# Main.net
KiCad netlist of a schematic drawn in Altium Designer
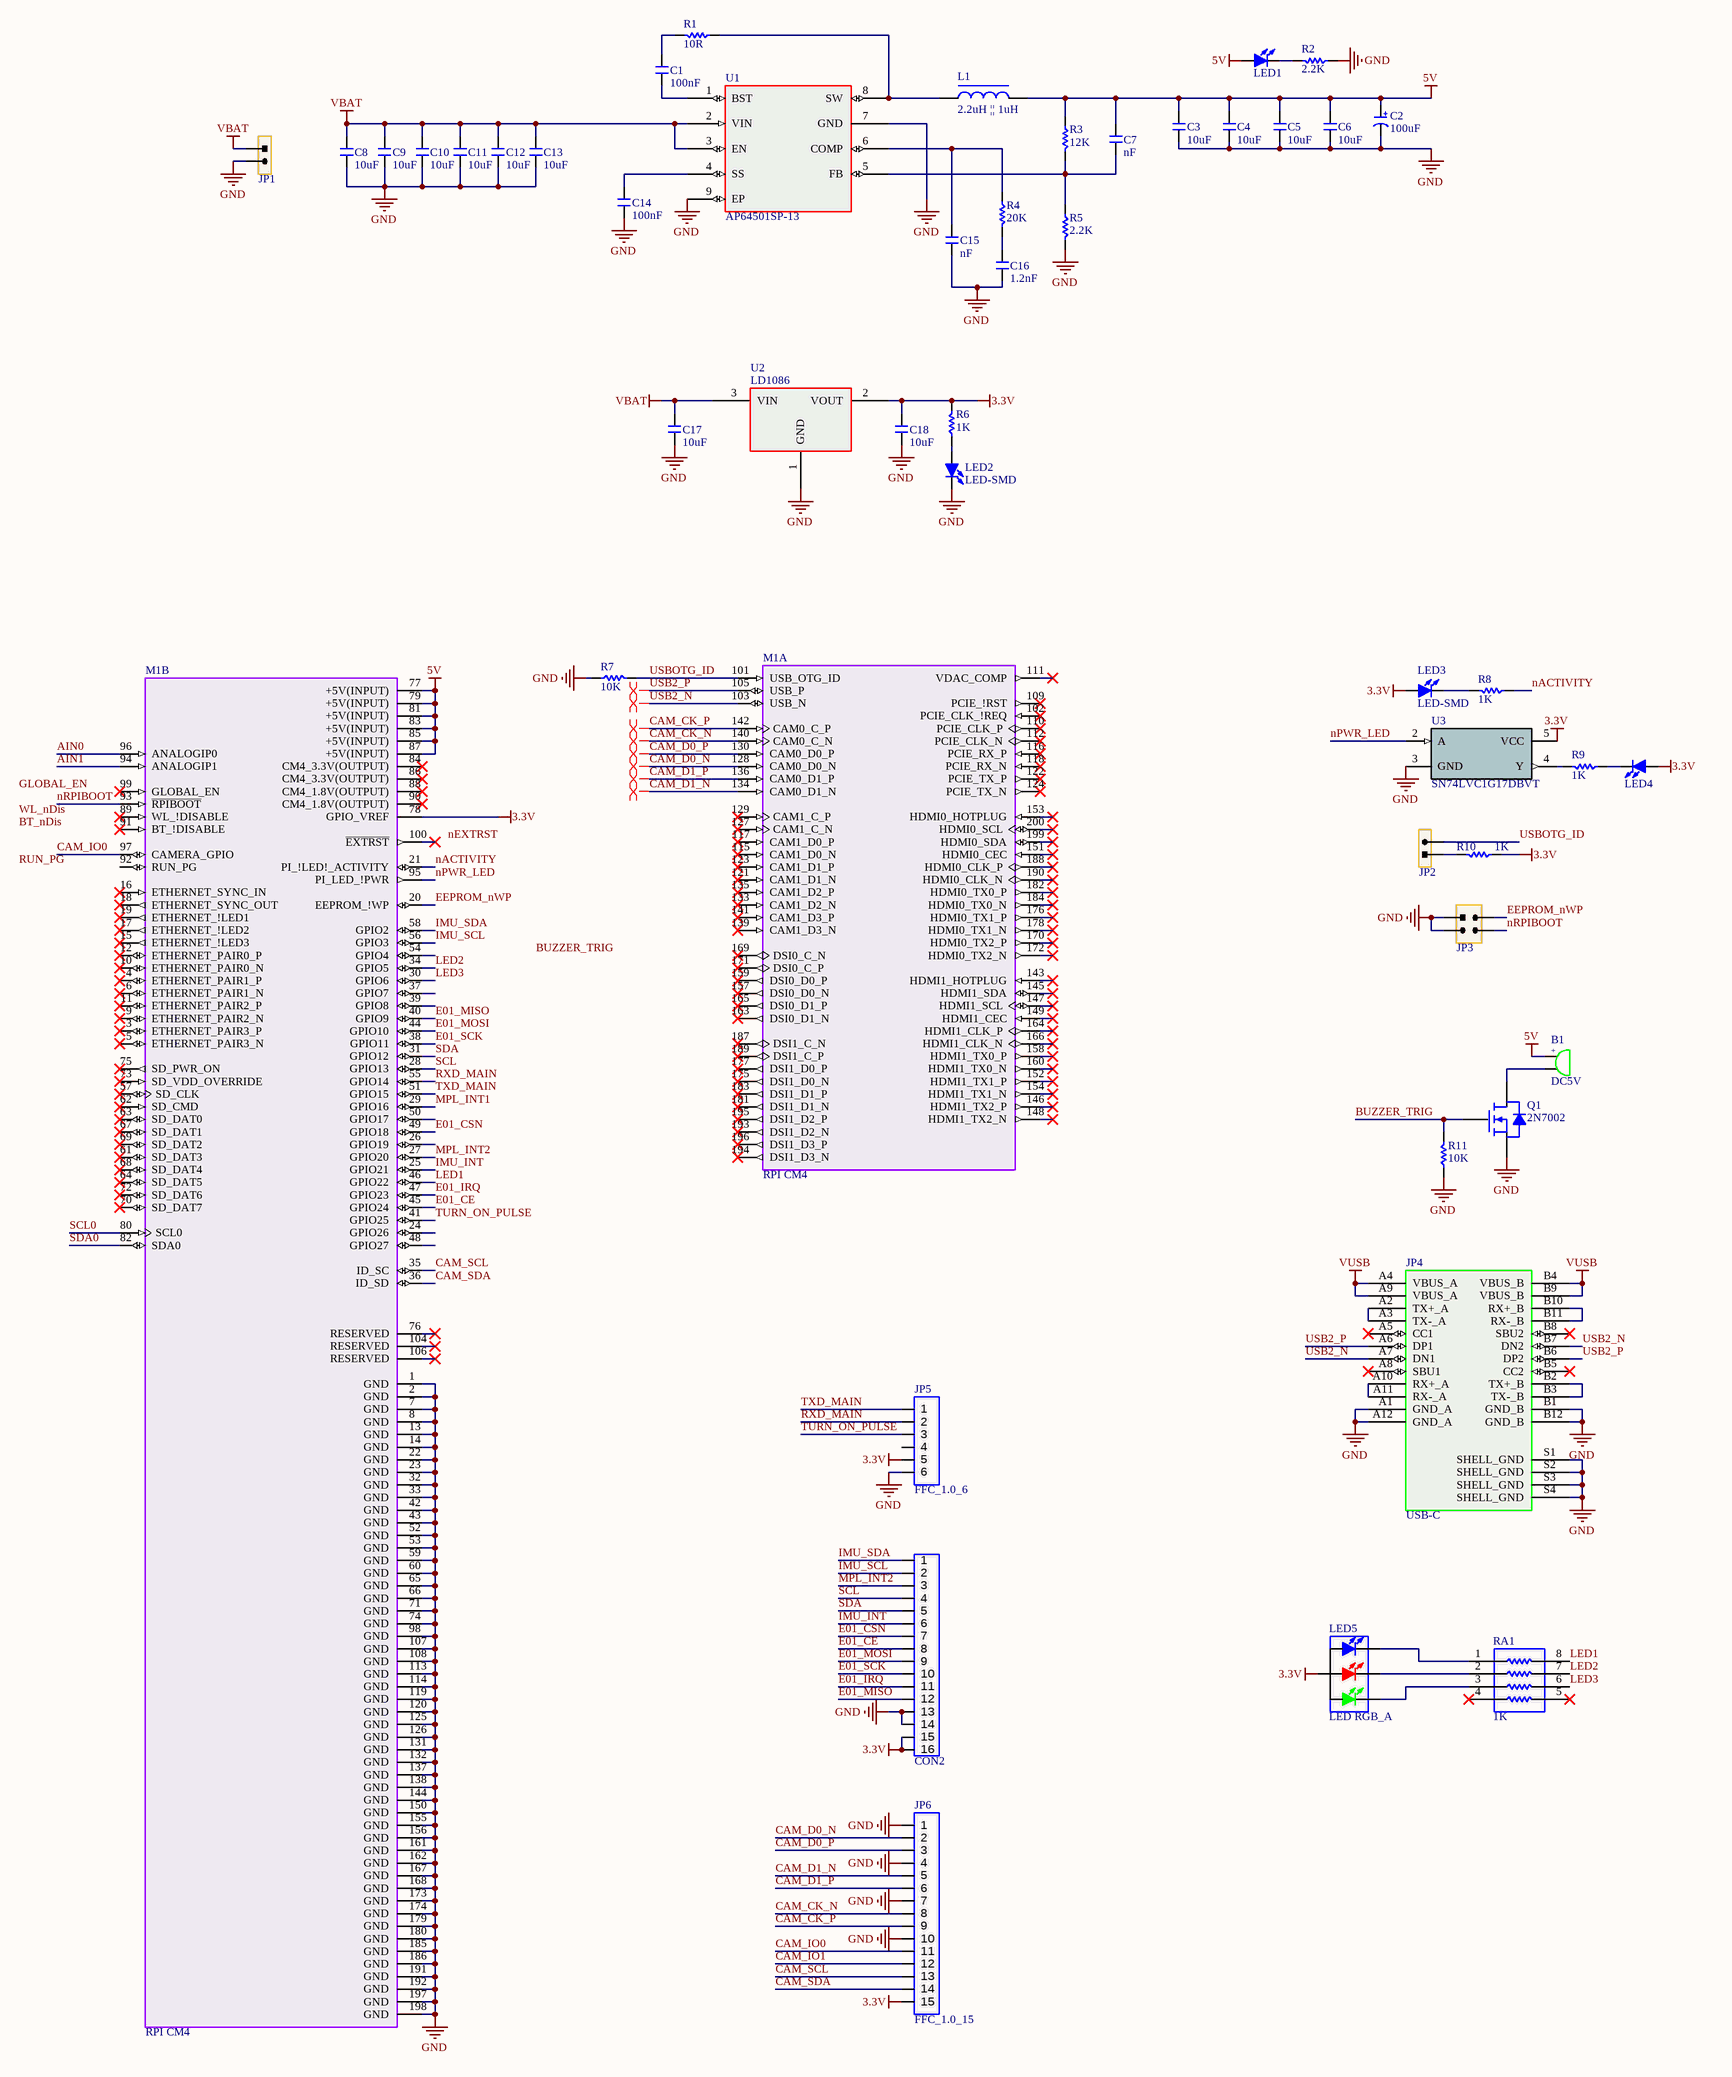
[diagram p0: Main.SchDoc]

(export (version "E")
  (design (tool "Eeschema 10.0.6"))
  (components
    (comp (ref "B1")
      (value "DC5V")
      (footprint "Buzzer 6.5x12x8.5")
      (description "Active Piezo Electronic Buzzer Beep")
      (libsource (lib "IO (Power-USB-Serial-VGA-RJ-Audio-Buzzer)") (part "Buzzer"))
    )
    (comp (ref "C1")
      (value "100nF")
      (footprint "C 0603")
      (description "Non-polar patch capacitor")
      (libsource (lib "Passive (Resistor-Capacitor-Inductor-Veristor-Ferrite)") (part "C"))
    )
    (comp (ref "C2")
      (value "100uF")
      (footprint "CD D(7343)")
      (description "Solid Tantalum Chip Capacitor, Standard T491 Series - Industrial Grade")
      (libsource (lib "Passive (Resistor-Capacitor-Inductor-Veristor-Ferrite)") (part "C-CD"))
    )
    (comp (ref "C3")
      (value "10uF")
      (footprint "C 0805")
      (description "Non-polar patch capacitor")
      (libsource (lib "Passive (Resistor-Capacitor-Inductor-Veristor-Ferrite)") (part "C"))
    )
    (comp (ref "C4")
      (value "10uF")
      (footprint "C 0805")
      (description "Non-polar patch capacitor")
      (libsource (lib "Passive (Resistor-Capacitor-Inductor-Veristor-Ferrite)") (part "C"))
    )
    (comp (ref "C5")
      (value "10uF")
      (footprint "C 0805")
      (description "Non-polar patch capacitor")
      (libsource (lib "Passive (Resistor-Capacitor-Inductor-Veristor-Ferrite)") (part "C"))
    )
    (comp (ref "C6")
      (value "10uF")
      (footprint "C 0805")
      (description "Non-polar patch capacitor")
      (libsource (lib "Passive (Resistor-Capacitor-Inductor-Veristor-Ferrite)") (part "C"))
    )
    (comp (ref "C7")
      (value "nF")
      (footprint "C 0603")
      (description "Non-polar patch capacitor")
      (libsource (lib "Passive (Resistor-Capacitor-Inductor-Veristor-Ferrite)") (part "C"))
    )
    (comp (ref "C8")
      (value "10uF")
      (footprint "C 0805")
      (description "Non-polar patch capacitor")
      (libsource (lib "Passive (Resistor-Capacitor-Inductor-Veristor-Ferrite)") (part "C"))
    )
    (comp (ref "C9")
      (value "10uF")
      (footprint "C 0805")
      (description "Non-polar patch capacitor")
      (libsource (lib "Passive (Resistor-Capacitor-Inductor-Veristor-Ferrite)") (part "C"))
    )
    (comp (ref "C10")
      (value "10uF")
      (footprint "C 0805")
      (description "Non-polar patch capacitor")
      (libsource (lib "Passive (Resistor-Capacitor-Inductor-Veristor-Ferrite)") (part "C"))
    )
    (comp (ref "C11")
      (value "10uF")
      (footprint "C 0805")
      (description "Non-polar patch capacitor")
      (libsource (lib "Passive (Resistor-Capacitor-Inductor-Veristor-Ferrite)") (part "C"))
    )
    (comp (ref "C12")
      (value "10uF")
      (footprint "C 0805")
      (description "Non-polar patch capacitor")
      (libsource (lib "Passive (Resistor-Capacitor-Inductor-Veristor-Ferrite)") (part "C"))
    )
    (comp (ref "C13")
      (value "10uF")
      (footprint "C 0805")
      (description "Non-polar patch capacitor")
      (libsource (lib "Passive (Resistor-Capacitor-Inductor-Veristor-Ferrite)") (part "C"))
    )
    (comp (ref "C14")
      (value "100nF")
      (footprint "C 0603")
      (description "Non-polar patch capacitor")
      (libsource (lib "Passive (Resistor-Capacitor-Inductor-Veristor-Ferrite)") (part "C"))
    )
    (comp (ref "C15")
      (value "nF")
      (footprint "C 0603")
      (description "Non-polar patch capacitor")
      (libsource (lib "Passive (Resistor-Capacitor-Inductor-Veristor-Ferrite)") (part "C"))
    )
    (comp (ref "C16")
      (value "1.2nF")
      (footprint "C 0603")
      (description "Non-polar patch capacitor")
      (libsource (lib "Passive (Resistor-Capacitor-Inductor-Veristor-Ferrite)") (part "C"))
    )
    (comp (ref "C17")
      (value "10uF")
      (footprint "C 0805")
      (description "Non-polar patch capacitor")
      (libsource (lib "Passive (Resistor-Capacitor-Inductor-Veristor-Ferrite)") (part "C"))
    )
    (comp (ref "C18")
      (value "10uF")
      (footprint "C 0805")
      (description "Non-polar patch capacitor")
      (libsource (lib "Passive (Resistor-Capacitor-Inductor-Veristor-Ferrite)") (part "C"))
    )
    (comp (ref "CON2")
      (value "FFC_0.5_16")
      (footprint "FFC_0.5_16")
      (description "FFC")
      (libsource (lib "FPC") (part "FFC_0.5_16"))
    )
    (comp (ref "JP1")
      (value "HDR-1X2")
      (footprint "XH2.54-2P_H")
      (description "2P Connector")
      (libsource (lib "Connectors") (part "Header 2"))
    )
    (comp (ref "JP2")
      (value "HDR-1X2")
      (footprint "HDR-1X2")
      (description "2P Connector")
      (libsource (lib "") (part "Header 2_1"))
    )
    (comp (ref "JP3")
      (value "Header2X2")
      (footprint "HDR-2X2")
      (description "2*2P Connector")
      (libsource (lib "Connectors") (part "Header 2X2"))
    )
    (comp (ref "JP4")
      (value "USB-C")
      (footprint "USB-C-RIGHT")
      (libsource (lib "IO (Power-USB-Serial-VGA-RJ-Audio-Buzzer)") (part "USB-C-RIGHT"))
    )
    (comp (ref "JP5")
      (value "FFC_1.0_6")
      (footprint "FFC_1.0_6_BT")
      (description "FFC")
      (libsource (lib "FPC") (part "FFC_1.0_6"))
    )
    (comp (ref "JP6")
      (value "FFC_1.0_15")
      (footprint "FFC_1.0_15_BT")
      (description "FFC")
      (libsource (lib "FPC") (part "FFC_1.0_15"))
    )
    (comp (ref "L1")
      (value "2.2uH Ζ 1uH")
      (footprint "CD53")
      (description "Chip power inductor")
      (libsource (lib "Passive (Resistor-Capacitor-Inductor-Veristor-Ferrite)") (part "L-CD"))
    )
    (comp (ref "LED1")
      (value "LED-SMD")
      (footprint "LED 0603R")
      (description "Patch LED")
      (libsource (lib "LED") (part "LED-SMD"))
    )
    (comp (ref "LED2")
      (value "LED-SMD")
      (footprint "LED 0603R")
      (description "Patch LED")
      (libsource (lib "LED") (part "LED-SMD"))
    )
    (comp (ref "LED3")
      (value "LED-SMD")
      (footprint "LED 0603Y")
      (description "Patch LED")
      (libsource (lib "LED") (part "LED-SMD"))
    )
    (comp (ref "LED4")
      (value "LED-SMD")
      (footprint "LED 0603R")
      (description "Patch LED")
      (libsource (lib "LED") (part "LED-SMD"))
    )
    (comp (ref "LED5")
      (value "LED RGB_A")
      (footprint "RGB-3535-A")
      (libsource (lib "LED") (part "LED RGB_A"))
    )
    (comp (ref "M1") (value "RPI CM4") (footprint "CM4") (libsource (lib "Raspberry pi") (part "CM4")))
    (comp (ref "Q1")
      (value "2N7002")
      (footprint "SOT23-3L")
      (description "N-Channel Enhancement Mode Field Effect Transistor")
      (libsource (lib "Transistor") (part "2N7002-SMD"))
    )
    (comp (ref "R1")
      (value "10R")
      (footprint "R 0603")
      (description "Chip resistor")
      (libsource (lib "Passive (Resistor-Capacitor-Inductor-Veristor-Ferrite)") (part "R"))
    )
    (comp (ref "R2")
      (value "2.2K")
      (footprint "R 0603")
      (description "Chip resistor")
      (libsource (lib "Passive (Resistor-Capacitor-Inductor-Veristor-Ferrite)") (part "R"))
    )
    (comp (ref "R3")
      (value "12K")
      (footprint "R 0603")
      (description "Chip resistor")
      (libsource (lib "Passive (Resistor-Capacitor-Inductor-Veristor-Ferrite)") (part "R"))
    )
    (comp (ref "R4")
      (value "20K")
      (footprint "R 0603")
      (description "Chip resistor")
      (libsource (lib "Passive (Resistor-Capacitor-Inductor-Veristor-Ferrite)") (part "R"))
    )
    (comp (ref "R5")
      (value "2.2K")
      (footprint "R 0603")
      (description "Chip resistor")
      (libsource (lib "Passive (Resistor-Capacitor-Inductor-Veristor-Ferrite)") (part "R"))
    )
    (comp (ref "R6")
      (value "1K")
      (footprint "R 0603")
      (description "Chip resistor")
      (libsource (lib "Passive (Resistor-Capacitor-Inductor-Veristor-Ferrite)") (part "R"))
    )
    (comp (ref "R7")
      (value "10K")
      (footprint "R 0603")
      (description "Chip resistor")
      (libsource (lib "Passive (Resistor-Capacitor-Inductor-Veristor-Ferrite)") (part "R"))
    )
    (comp (ref "R8")
      (value "1K")
      (footprint "R 0603")
      (description "Chip resistor")
      (libsource (lib "Passive (Resistor-Capacitor-Inductor-Veristor-Ferrite)") (part "R"))
    )
    (comp (ref "R9")
      (value "1K")
      (footprint "R 0603")
      (description "Chip resistor")
      (libsource (lib "Passive (Resistor-Capacitor-Inductor-Veristor-Ferrite)") (part "R"))
    )
    (comp (ref "R10")
      (value "1K")
      (footprint "R 0603")
      (description "Chip resistor")
      (libsource (lib "Passive (Resistor-Capacitor-Inductor-Veristor-Ferrite)") (part "R"))
    )
    (comp (ref "R11")
      (value "10K")
      (footprint "R 0603")
      (description "Chip resistor")
      (libsource (lib "Passive (Resistor-Capacitor-Inductor-Veristor-Ferrite)") (part "R"))
    )
    (comp (ref "RA1")
      (value "1K")
      (footprint "RA1206 (4x0603)")
      (description "4 way Chip Resistor Array")
      (libsource (lib "Passive (Resistor-Capacitor-Inductor-Veristor-Ferrite)") (part "R-ARR"))
    )
    (comp (ref "U1")
      (value "AP64501SP-13")
      (footprint "SOP8_M-EP")
      (libsource (lib "Integrated Circuit") (part "AP64501SP-13"))
    )
    (comp (ref "U2")
      (value "LD1086")
      (footprint "TO252")
      (description "Linear Voltage Regulator IC 1 Output 1.5A DPAK")
      (libsource (lib "Integrated Circuit") (part "LD1086"))
    )
    (comp (ref "U3")
      (value "SN74LVC1G17DBVT")
      (footprint "SOT23-5M")
      (description "Single 1.65-V to 5.5-V buffer with Schmitt-Trigger inputs")
      (libsource (lib "Integrated Circuit") (part "SN74LVC1G17DBVT"))
    )
  )
  (nets
    (net (code "1") (name "/AIN0") (class "Default")
      (node (ref "M1") (pin "96") (pinfunction "ANALOGIP0_96") (pintype "input"))
    )
    (net (code "2") (name "/AIN1") (class "Default")
      (node (ref "M1") (pin "94") (pinfunction "ANALOGIP1_94") (pintype "input"))
    )
    (net (code "4") (name "/BUZZER_TRIG") (class "Default")
      (node (ref "Q1") (pin "1") (pinfunction "G_1") (pintype "passive"))
      (node (ref "R11") (pin "2") (pinfunction "2_2") (pintype "passive"))
    )
    (net (code "5") (name "/CAM_CK_N") (class "Default")
      (node (ref "JP6") (pin "8") (pinfunction "8_8") (pintype "passive"))
      (node (ref "M1") (pin "140") (pinfunction "CAM0_C_N_140") (pintype "input"))
    )
    (net (code "6") (name "/CAM_CK_P") (class "Default")
      (node (ref "JP6") (pin "9") (pinfunction "9_9") (pintype "passive"))
      (node (ref "M1") (pin "142") (pinfunction "CAM0_C_P_142") (pintype "input"))
    )
    (net (code "7") (name "/CAM_D0_N") (class "Default")
      (node (ref "JP6") (pin "2") (pinfunction "2_2") (pintype "passive"))
      (node (ref "M1") (pin "128") (pinfunction "CAM0_D0_N_128") (pintype "input"))
    )
    (net (code "8") (name "/CAM_D0_P") (class "Default")
      (node (ref "JP6") (pin "3") (pinfunction "3_3") (pintype "passive"))
      (node (ref "M1") (pin "130") (pinfunction "CAM0_D0_P_130") (pintype "input"))
    )
    (net (code "9") (name "/CAM_D1_N") (class "Default")
      (node (ref "JP6") (pin "5") (pinfunction "5_5") (pintype "passive"))
      (node (ref "M1") (pin "134") (pinfunction "CAM0_D1_N_134") (pintype "input"))
    )
    (net (code "10") (name "/CAM_D1_P") (class "Default")
      (node (ref "JP6") (pin "6") (pinfunction "6_6") (pintype "passive"))
      (node (ref "M1") (pin "136") (pinfunction "CAM0_D1_P_136") (pintype "input"))
    )
    (net (code "11") (name "/CAM_IO0") (class "Default")
      (node (ref "JP6") (pin "11") (pinfunction "11_11") (pintype "passive"))
      (node (ref "M1") (pin "97") (pinfunction "CAMERA_GPIO_97") (pintype "bidirectional"))
    )
    (net (code "12") (name "/CAM_IO1") (class "Default")
      (node (ref "JP6") (pin "12") (pinfunction "12_12") (pintype "passive"))
    )
    (net (code "13") (name "/CAM_SCL") (class "Default")
      (node (ref "JP6") (pin "13") (pinfunction "13_13") (pintype "passive"))
      (node (ref "M1") (pin "35") (pinfunction "ID_SC_35") (pintype "bidirectional"))
    )
    (net (code "14") (name "/CAM_SDA") (class "Default")
      (node (ref "JP6") (pin "14") (pinfunction "14_14") (pintype "passive"))
      (node (ref "M1") (pin "36") (pinfunction "ID_SD_36") (pintype "bidirectional"))
    )
    (net (code "15") (name "/E01_CE") (class "Default")
      (node (ref "CON2") (pin "8") (pinfunction "8_8") (pintype "passive"))
      (node (ref "M1") (pin "45") (pinfunction "GPIO24_45") (pintype "bidirectional"))
    )
    (net (code "16") (name "/E01_CSN") (class "Default")
      (node (ref "CON2") (pin "7") (pinfunction "7_7") (pintype "passive"))
      (node (ref "M1") (pin "49") (pinfunction "GPIO18_49") (pintype "bidirectional"))
    )
    (net (code "17") (name "/E01_IRQ") (class "Default")
      (node (ref "CON2") (pin "11") (pinfunction "11_11") (pintype "passive"))
      (node (ref "M1") (pin "47") (pinfunction "GPIO23_47") (pintype "bidirectional"))
    )
    (net (code "18") (name "/E01_MISO") (class "Default")
      (node (ref "CON2") (pin "12") (pinfunction "12_12") (pintype "passive"))
      (node (ref "M1") (pin "40") (pinfunction "GPIO9_40") (pintype "bidirectional"))
    )
    (net (code "19") (name "/E01_MOSI") (class "Default")
      (node (ref "CON2") (pin "9") (pinfunction "9_9") (pintype "passive"))
      (node (ref "M1") (pin "44") (pinfunction "GPIO10_44") (pintype "bidirectional"))
    )
    (net (code "20") (name "/E01_SCK") (class "Default")
      (node (ref "CON2") (pin "10") (pinfunction "10_10") (pintype "passive"))
      (node (ref "M1") (pin "38") (pinfunction "GPIO11_38") (pintype "bidirectional"))
    )
    (net (code "21") (name "/EEPROM_nWP") (class "Default")
      (node (ref "JP3") (pin "2") (pintype "passive"))
      (node (ref "M1") (pin "20") (pinfunction "EEPROM_!WP_20") (pintype "bidirectional"))
    )
    (net (code "23") (name "/IMU_INT") (class "Default")
      (node (ref "CON2") (pin "6") (pinfunction "6_6") (pintype "passive"))
      (node (ref "M1") (pin "25") (pinfunction "GPIO21_25") (pintype "bidirectional"))
    )
    (net (code "24") (name "/IMU_SCL") (class "Default")
      (node (ref "CON2") (pin "2") (pinfunction "2_2") (pintype "passive"))
      (node (ref "M1") (pin "56") (pinfunction "GPIO3_56") (pintype "bidirectional"))
    )
    (net (code "25") (name "/IMU_SDA") (class "Default")
      (node (ref "CON2") (pin "1") (pinfunction "1_1") (pintype "passive"))
      (node (ref "M1") (pin "58") (pinfunction "GPIO2_58") (pintype "bidirectional"))
    )
    (net (code "26") (name "/LED1") (class "Default")
      (node (ref "M1") (pin "46") (pinfunction "GPIO22_46") (pintype "bidirectional"))
      (node (ref "RA1") (pin "8") (pinfunction "8_8") (pintype "passive"))
    )
    (net (code "27") (name "/LED2") (class "Default")
      (node (ref "M1") (pin "34") (pinfunction "GPIO5_34") (pintype "bidirectional"))
      (node (ref "RA1") (pin "7") (pinfunction "7_7") (pintype "passive"))
    )
    (net (code "28") (name "/LED3") (class "Default")
      (node (ref "M1") (pin "30") (pinfunction "GPIO6_30") (pintype "bidirectional"))
      (node (ref "RA1") (pin "6") (pinfunction "6_6") (pintype "passive"))
    )
    (net (code "29") (name "/MPL_INT1") (class "Default")
      (node (ref "M1") (pin "29") (pinfunction "GPIO16_29") (pintype "bidirectional"))
    )
    (net (code "30") (name "/MPL_INT2") (class "Default")
      (node (ref "CON2") (pin "3") (pinfunction "3_3") (pintype "passive"))
      (node (ref "M1") (pin "27") (pinfunction "GPIO20_27") (pintype "bidirectional"))
    )
    (net (code "32") (name "/RXD_MAIN") (class "Default")
      (node (ref "JP5") (pin "2") (pinfunction "2_2") (pintype "passive"))
      (node (ref "M1") (pin "55") (pinfunction "GPIO14_55") (pintype "bidirectional"))
    )
    (net (code "33") (name "/SCL") (class "Default")
      (node (ref "CON2") (pin "4") (pinfunction "4_4") (pintype "passive"))
      (node (ref "M1") (pin "28") (pinfunction "GPIO13_28") (pintype "bidirectional"))
    )
    (net (code "34") (name "/SCL0") (class "Default")
      (node (ref "M1") (pin "80") (pinfunction "SCL0_80") (pintype "input"))
    )
    (net (code "35") (name "/SDA") (class "Default")
      (node (ref "CON2") (pin "5") (pinfunction "5_5") (pintype "passive"))
      (node (ref "M1") (pin "31") (pinfunction "GPIO12_31") (pintype "bidirectional"))
    )
    (net (code "36") (name "/SDA0") (class "Default")
      (node (ref "M1") (pin "82") (pinfunction "SDA0_82") (pintype "bidirectional"))
    )
    (net (code "37") (name "/TURN_ON_PULSE") (class "Default")
      (node (ref "JP5") (pin "3") (pinfunction "3_3") (pintype "passive"))
      (node (ref "M1") (pin "41") (pinfunction "GPIO25_41") (pintype "bidirectional"))
    )
    (net (code "38") (name "/TXD_MAIN") (class "Default")
      (node (ref "JP5") (pin "1") (pinfunction "1_1") (pintype "passive"))
      (node (ref "M1") (pin "51") (pinfunction "GPIO15_51") (pintype "bidirectional"))
    )
    (net (code "39") (name "/USB2_N") (class "Default")
      (node (ref "JP4") (pin "A7") (pinfunction "DN1_A7") (pintype "bidirectional"))
      (node (ref "JP4") (pin "B7") (pinfunction "DN2_B7") (pintype "bidirectional"))
      (node (ref "M1") (pin "103") (pinfunction "USB_N_103") (pintype "bidirectional"))
    )
    (net (code "40") (name "/USB2_P") (class "Default")
      (node (ref "JP4") (pin "A6") (pinfunction "DP1_A6") (pintype "bidirectional"))
      (node (ref "JP4") (pin "B6") (pinfunction "DP2_B6") (pintype "bidirectional"))
      (node (ref "M1") (pin "105") (pinfunction "USB_P_105") (pintype "bidirectional"))
    )
    (net (code "41") (name "/USBOTG_ID") (class "Default")
      (node (ref "JP2") (pin "2") (pintype "passive"))
      (node (ref "M1") (pin "101") (pinfunction "USB_OTG_ID_101") (pintype "input"))
      (node (ref "R7") (pin "2") (pinfunction "2_2") (pintype "passive"))
    )
    (net (code "43") (name "/nACTIVITY") (class "Default")
      (node (ref "M1") (pin "21") (pinfunction "PI_!LED!_ACTIVITY_21") (pintype "bidirectional"))
      (node (ref "R8") (pin "1") (pinfunction "1_1") (pintype "passive"))
    )
    (net (code "45") (name "/nPWR_LED") (class "Default")
      (node (ref "M1") (pin "95") (pinfunction "PI_LED_!PWR_95") (pintype "output"))
      (node (ref "U3") (pin "2") (pinfunction "A_2") (pintype "input"))
    )
    (net (code "46") (name "/nRPIBOOT") (class "Default")
      (node (ref "JP3") (pin "4") (pintype "passive"))
      (node (ref "M1") (pin "93") (pinfunction "~{RPIBOOT}_93") (pintype "input"))
    )
    (net (code "47") (name "3.3V") (class "Default")
      (node (ref "C18") (pin "1") (pinfunction "1_1") (pintype "passive"))
      (node (ref "CON2") (pin "15") (pinfunction "15_15") (pintype "passive"))
      (node (ref "CON2") (pin "16") (pinfunction "16_16") (pintype "passive"))
      (node (ref "JP5") (pin "5") (pinfunction "5_5") (pintype "passive"))
      (node (ref "JP6") (pin "15") (pinfunction "15_15") (pintype "passive"))
      (node (ref "LED3") (pin "1") (pinfunction "A_1") (pintype "passive"))
      (node (ref "LED4") (pin "1") (pinfunction "A_1") (pintype "passive"))
      (node (ref "LED5") (pin "3") (pinfunction "RED_A_3") (pintype "passive"))
      (node (ref "M1") (pin "78") (pinfunction "GPIO_VREF_78") (pintype "power_in"))
      (node (ref "R10") (pin "1") (pinfunction "1_1") (pintype "passive"))
      (node (ref "R6") (pin "2") (pinfunction "2_2") (pintype "passive"))
      (node (ref "U2") (pin "2") (pinfunction "VOUT_2") (pintype "power_in"))
      (node (ref "U3") (pin "5") (pinfunction "VCC_5") (pintype "power_in"))
    )
    (net (code "48") (name "5V") (class "Default")
      (node (ref "B1") (pin "A") (pinfunction "A_A") (pintype "passive"))
      (node (ref "C2") (pin "1") (pinfunction "A_1") (pintype "passive"))
      (node (ref "C3") (pin "1") (pinfunction "1_1") (pintype "passive"))
      (node (ref "C4") (pin "1") (pinfunction "1_1") (pintype "passive"))
      (node (ref "C5") (pin "1") (pinfunction "1_1") (pintype "passive"))
      (node (ref "C6") (pin "1") (pinfunction "1_1") (pintype "passive"))
      (node (ref "C7") (pin "1") (pinfunction "1_1") (pintype "passive"))
      (node (ref "L1") (pin "2") (pinfunction "2_2") (pintype "passive"))
      (node (ref "LED1") (pin "1") (pinfunction "A_1") (pintype "passive"))
      (node (ref "M1") (pin "77") (pinfunction "+5V(INPUT)_77") (pintype "power_in"))
      (node (ref "M1") (pin "79") (pinfunction "+5V(INPUT)_79") (pintype "power_in"))
      (node (ref "M1") (pin "81") (pinfunction "+5V(INPUT)_81") (pintype "power_in"))
      (node (ref "M1") (pin "83") (pinfunction "+5V(INPUT)_83") (pintype "power_in"))
      (node (ref "M1") (pin "85") (pinfunction "+5V(INPUT)_85") (pintype "power_in"))
      (node (ref "M1") (pin "87") (pinfunction "+5V(INPUT)_87") (pintype "power_in"))
      (node (ref "R3") (pin "1") (pinfunction "1_1") (pintype "passive"))
    )
    (net (code "49") (name "GND") (class "Default")
      (node (ref "C10") (pin "2") (pinfunction "2_2") (pintype "passive"))
      (node (ref "C11") (pin "2") (pinfunction "2_2") (pintype "passive"))
      (node (ref "C12") (pin "2") (pinfunction "2_2") (pintype "passive"))
      (node (ref "C13") (pin "2") (pinfunction "2_2") (pintype "passive"))
      (node (ref "C14") (pin "2") (pinfunction "2_2") (pintype "passive"))
      (node (ref "C15") (pin "2") (pinfunction "2_2") (pintype "passive"))
      (node (ref "C16") (pin "2") (pinfunction "2_2") (pintype "passive"))
      (node (ref "C17") (pin "2") (pinfunction "2_2") (pintype "passive"))
      (node (ref "C18") (pin "2") (pinfunction "2_2") (pintype "passive"))
      (node (ref "C2") (pin "2") (pinfunction "K_2") (pintype "passive"))
      (node (ref "C3") (pin "2") (pinfunction "2_2") (pintype "passive"))
      (node (ref "C4") (pin "2") (pinfunction "2_2") (pintype "passive"))
      (node (ref "C5") (pin "2") (pinfunction "2_2") (pintype "passive"))
      (node (ref "C6") (pin "2") (pinfunction "2_2") (pintype "passive"))
      (node (ref "C8") (pin "2") (pinfunction "2_2") (pintype "passive"))
      (node (ref "C9") (pin "2") (pinfunction "2_2") (pintype "passive"))
      (node (ref "CON2") (pin "13") (pinfunction "13_13") (pintype "passive"))
      (node (ref "CON2") (pin "14") (pinfunction "14_14") (pintype "passive"))
      (node (ref "JP1") (pin "2") (pintype "passive"))
      (node (ref "JP3") (pin "1") (pintype "passive"))
      (node (ref "JP3") (pin "3") (pintype "passive"))
      (node (ref "JP4") (pin "A1") (pinfunction "GND_A_A1") (pintype "power_in"))
      (node (ref "JP4") (pin "A12") (pinfunction "GND_A_A12") (pintype "power_in"))
      (node (ref "JP4") (pin "B1") (pinfunction "GND_B_B1") (pintype "power_in"))
      (node (ref "JP4") (pin "B12") (pinfunction "GND_B_B12") (pintype "power_in"))
      (node (ref "JP4") (pin "S1") (pinfunction "SHELL_GND_S1") (pintype "power_in"))
      (node (ref "JP4") (pin "S2") (pinfunction "SHELL_GND_S2") (pintype "power_in"))
      (node (ref "JP4") (pin "S3") (pinfunction "SHELL_GND_S3") (pintype "power_in"))
      (node (ref "JP4") (pin "S4") (pinfunction "SHELL_GND_S4") (pintype "power_in"))
      (node (ref "JP5") (pin "6") (pinfunction "6_6") (pintype "passive"))
      (node (ref "JP6") (pin "1") (pinfunction "1_1") (pintype "passive"))
      (node (ref "JP6") (pin "10") (pinfunction "10_10") (pintype "passive"))
      (node (ref "JP6") (pin "4") (pinfunction "4_4") (pintype "passive"))
      (node (ref "JP6") (pin "7") (pinfunction "7_7") (pintype "passive"))
      (node (ref "LED2") (pin "2") (pinfunction "K_2") (pintype "passive"))
      (node (ref "M1") (pin "1") (pinfunction "GND_1") (pintype "power_in"))
      (node (ref "M1") (pin "107") (pinfunction "GND_107") (pintype "power_in"))
      (node (ref "M1") (pin "108") (pinfunction "GND_108") (pintype "power_in"))
      (node (ref "M1") (pin "113") (pinfunction "GND_113") (pintype "power_in"))
      (node (ref "M1") (pin "114") (pinfunction "GND_114") (pintype "power_in"))
      (node (ref "M1") (pin "119") (pinfunction "GND_119") (pintype "power_in"))
      (node (ref "M1") (pin "120") (pinfunction "GND_120") (pintype "power_in"))
      (node (ref "M1") (pin "125") (pinfunction "GND_125") (pintype "power_in"))
      (node (ref "M1") (pin "126") (pinfunction "GND_126") (pintype "power_in"))
      (node (ref "M1") (pin "13") (pinfunction "GND_13") (pintype "power_in"))
      (node (ref "M1") (pin "131") (pinfunction "GND_131") (pintype "power_in"))
      (node (ref "M1") (pin "132") (pinfunction "GND_132") (pintype "power_in"))
      (node (ref "M1") (pin "137") (pinfunction "GND_137") (pintype "power_in"))
      (node (ref "M1") (pin "138") (pinfunction "GND_138") (pintype "power_in"))
      (node (ref "M1") (pin "14") (pinfunction "GND_14") (pintype "power_in"))
      (node (ref "M1") (pin "144") (pinfunction "GND_144") (pintype "power_in"))
      (node (ref "M1") (pin "150") (pinfunction "GND_150") (pintype "power_in"))
      (node (ref "M1") (pin "155") (pinfunction "GND_155") (pintype "power_in"))
      (node (ref "M1") (pin "156") (pinfunction "GND_156") (pintype "power_in"))
      (node (ref "M1") (pin "161") (pinfunction "GND_161") (pintype "power_in"))
      (node (ref "M1") (pin "162") (pinfunction "GND_162") (pintype "power_in"))
      (node (ref "M1") (pin "167") (pinfunction "GND_167") (pintype "power_in"))
      (node (ref "M1") (pin "168") (pinfunction "GND_168") (pintype "power_in"))
      (node (ref "M1") (pin "173") (pinfunction "GND_173") (pintype "power_in"))
      (node (ref "M1") (pin "174") (pinfunction "GND_174") (pintype "power_in"))
      (node (ref "M1") (pin "179") (pinfunction "GND_179") (pintype "power_in"))
      (node (ref "M1") (pin "180") (pinfunction "GND_180") (pintype "power_in"))
      (node (ref "M1") (pin "185") (pinfunction "GND_185") (pintype "power_in"))
      (node (ref "M1") (pin "186") (pinfunction "GND_186") (pintype "power_in"))
      (node (ref "M1") (pin "191") (pinfunction "GND_191") (pintype "power_in"))
      (node (ref "M1") (pin "192") (pinfunction "GND_192") (pintype "power_in"))
      (node (ref "M1") (pin "197") (pinfunction "GND_197") (pintype "power_in"))
      (node (ref "M1") (pin "198") (pinfunction "GND_198") (pintype "power_in"))
      (node (ref "M1") (pin "2") (pinfunction "GND_2") (pintype "power_in"))
      (node (ref "M1") (pin "22") (pinfunction "GND_22") (pintype "power_in"))
      (node (ref "M1") (pin "23") (pinfunction "GND_23") (pintype "power_in"))
      (node (ref "M1") (pin "32") (pinfunction "GND_32") (pintype "power_in"))
      (node (ref "M1") (pin "33") (pinfunction "GND_33") (pintype "power_in"))
      (node (ref "M1") (pin "42") (pinfunction "GND_42") (pintype "power_in"))
      (node (ref "M1") (pin "43") (pinfunction "GND_43") (pintype "power_in"))
      (node (ref "M1") (pin "52") (pinfunction "GND_52") (pintype "power_in"))
      (node (ref "M1") (pin "53") (pinfunction "GND_53") (pintype "power_in"))
      (node (ref "M1") (pin "59") (pinfunction "GND_59") (pintype "power_in"))
      (node (ref "M1") (pin "60") (pinfunction "GND_60") (pintype "power_in"))
      (node (ref "M1") (pin "65") (pinfunction "GND_65") (pintype "power_in"))
      (node (ref "M1") (pin "66") (pinfunction "GND_66") (pintype "power_in"))
      (node (ref "M1") (pin "7") (pinfunction "GND_7") (pintype "power_in"))
      (node (ref "M1") (pin "71") (pinfunction "GND_71") (pintype "power_in"))
      (node (ref "M1") (pin "74") (pinfunction "GND_74") (pintype "power_in"))
      (node (ref "M1") (pin "8") (pinfunction "GND_8") (pintype "power_in"))
      (node (ref "M1") (pin "98") (pinfunction "GND_98") (pintype "power_in"))
      (node (ref "Q1") (pin "2") (pinfunction "S_2") (pintype "passive"))
      (node (ref "R11") (pin "1") (pinfunction "1_1") (pintype "passive"))
      (node (ref "R2") (pin "1") (pinfunction "1_1") (pintype "passive"))
      (node (ref "R5") (pin "2") (pinfunction "2_2") (pintype "passive"))
      (node (ref "R7") (pin "1") (pinfunction "1_1") (pintype "passive"))
      (node (ref "U1") (pin "7") (pinfunction "GND_7") (pintype "power_in"))
      (node (ref "U1") (pin "9") (pinfunction "EP_9") (pintype "bidirectional"))
      (node (ref "U2") (pin "1") (pinfunction "GND_1") (pintype "power_in"))
      (node (ref "U3") (pin "3") (pinfunction "GND_3") (pintype "power_in"))
    )
    (net (code "50") (name "Net-(C1-Pad1)") (class "Default")
      (node (ref "C1") (pin "1") (pinfunction "1_1") (pintype "passive"))
      (node (ref "R1") (pin "2") (pinfunction "2_2") (pintype "passive"))
    )
    (net (code "51") (name "Net-(C16-Pad1)") (class "Default")
      (node (ref "C16") (pin "1") (pinfunction "1_1") (pintype "passive"))
      (node (ref "R4") (pin "2") (pinfunction "2_2") (pintype "passive"))
    )
    (net (code "52") (name "Net-(JP2-Pad1)") (class "Default")
      (node (ref "JP2") (pin "1") (pintype "passive"))
      (node (ref "R10") (pin "2") (pinfunction "2_2") (pintype "passive"))
    )
    (net (code "53") (name "Net-(JP4-RX+_A)") (class "Default")
      (node (ref "JP4") (pin "A10") (pinfunction "RX+_A_A10") (pintype "power_in"))
      (node (ref "JP4") (pin "A11") (pinfunction "RX-_A_A11") (pintype "power_in"))
    )
    (net (code "54") (name "Net-(JP4-RX+_B)") (class "Default")
      (node (ref "JP4") (pin "B10") (pinfunction "RX+_B_B10") (pintype "power_in"))
      (node (ref "JP4") (pin "B11") (pinfunction "RX-_B_B11") (pintype "power_in"))
    )
    (net (code "55") (name "Net-(JP4-TX+_A)") (class "Default")
      (node (ref "JP4") (pin "A2") (pinfunction "TX+_A_A2") (pintype "power_in"))
      (node (ref "JP4") (pin "A3") (pinfunction "TX-_A_A3") (pintype "power_in"))
    )
    (net (code "56") (name "Net-(JP4-TX+_B)") (class "Default")
      (node (ref "JP4") (pin "B2") (pinfunction "TX+_B_B2") (pintype "power_in"))
      (node (ref "JP4") (pin "B3") (pinfunction "TX-_B_B3") (pintype "power_in"))
    )
    (net (code "57") (name "Net-(LED1-K)") (class "Default")
      (node (ref "LED1") (pin "2") (pinfunction "K_2") (pintype "passive"))
      (node (ref "R2") (pin "2") (pinfunction "2_2") (pintype "passive"))
    )
    (net (code "58") (name "Net-(LED2-A)") (class "Default")
      (node (ref "LED2") (pin "1") (pinfunction "A_1") (pintype "passive"))
      (node (ref "R6") (pin "1") (pinfunction "1_1") (pintype "passive"))
    )
    (net (code "59") (name "Net-(LED3-K)") (class "Default")
      (node (ref "LED3") (pin "2") (pinfunction "K_2") (pintype "passive"))
      (node (ref "R8") (pin "2") (pinfunction "2_2") (pintype "passive"))
    )
    (net (code "60") (name "Net-(LED4-K)") (class "Default")
      (node (ref "LED4") (pin "2") (pinfunction "K_2") (pintype "passive"))
      (node (ref "R9") (pin "1") (pinfunction "1_1") (pintype "passive"))
    )
    (net (code "61") (name "Net-(LED5-BULE_K)") (class "Default")
      (node (ref "LED5") (pin "1") (pinfunction "BULE_K_1") (pintype "passive"))
      (node (ref "RA1") (pin "1") (pinfunction "1_1") (pintype "passive"))
    )
    (net (code "62") (name "Net-(LED5-GREEN_K)") (class "Default")
      (node (ref "LED5") (pin "2") (pinfunction "GREEN_K_2") (pintype "passive"))
      (node (ref "RA1") (pin "3") (pinfunction "3_3") (pintype "passive"))
    )
    (net (code "63") (name "Net-(LED5-RED_K)") (class "Default")
      (node (ref "LED5") (pin "4") (pinfunction "RED_K_4") (pintype "passive"))
      (node (ref "RA1") (pin "2") (pinfunction "2_2") (pintype "passive"))
    )
    (net (code "64") (name "Net-(Q1-D)") (class "Default")
      (node (ref "B1") (pin "K") (pinfunction "K_K") (pintype "passive"))
      (node (ref "Q1") (pin "3") (pinfunction "D_3") (pintype "passive"))
    )
    (net (code "65") (name "Net-(U1-BST)") (class "Default")
      (node (ref "C1") (pin "2") (pinfunction "2_2") (pintype "passive"))
      (node (ref "U1") (pin "1") (pinfunction "BST_1") (pintype "bidirectional"))
    )
    (net (code "66") (name "Net-(U1-COMP)") (class "Default")
      (node (ref "C15") (pin "1") (pinfunction "1_1") (pintype "passive"))
      (node (ref "R4") (pin "1") (pinfunction "1_1") (pintype "passive"))
      (node (ref "U1") (pin "6") (pinfunction "COMP_6") (pintype "bidirectional"))
    )
    (net (code "67") (name "Net-(U1-FB)") (class "Default")
      (node (ref "C7") (pin "2") (pinfunction "2_2") (pintype "passive"))
      (node (ref "R3") (pin "2") (pinfunction "2_2") (pintype "passive"))
      (node (ref "R5") (pin "1") (pinfunction "1_1") (pintype "passive"))
      (node (ref "U1") (pin "5") (pinfunction "FB_5") (pintype "bidirectional"))
    )
    (net (code "68") (name "Net-(U1-SS)") (class "Default")
      (node (ref "C14") (pin "1") (pinfunction "1_1") (pintype "passive"))
      (node (ref "U1") (pin "4") (pinfunction "SS_4") (pintype "bidirectional"))
    )
    (net (code "69") (name "Net-(U1-SW)") (class "Default")
      (node (ref "L1") (pin "1") (pinfunction "1_1") (pintype "passive"))
      (node (ref "R1") (pin "1") (pinfunction "1_1") (pintype "passive"))
      (node (ref "U1") (pin "8") (pinfunction "SW_8") (pintype "bidirectional"))
    )
    (net (code "70") (name "Net-(U3-Y)") (class "Default")
      (node (ref "R9") (pin "2") (pinfunction "2_2") (pintype "passive"))
      (node (ref "U3") (pin "4") (pinfunction "Y_4") (pintype "output"))
    )
    (net (code "71") (name "VBAT") (class "Default")
      (node (ref "C10") (pin "1") (pinfunction "1_1") (pintype "passive"))
      (node (ref "C11") (pin "1") (pinfunction "1_1") (pintype "passive"))
      (node (ref "C12") (pin "1") (pinfunction "1_1") (pintype "passive"))
      (node (ref "C13") (pin "1") (pinfunction "1_1") (pintype "passive"))
      (node (ref "C17") (pin "1") (pinfunction "1_1") (pintype "passive"))
      (node (ref "C8") (pin "1") (pinfunction "1_1") (pintype "passive"))
      (node (ref "C9") (pin "1") (pinfunction "1_1") (pintype "passive"))
      (node (ref "JP1") (pin "1") (pintype "passive"))
      (node (ref "U1") (pin "2") (pinfunction "VIN_2") (pintype "input"))
      (node (ref "U1") (pin "3") (pinfunction "EN_3") (pintype "bidirectional"))
      (node (ref "U2") (pin "3") (pinfunction "VIN_3") (pintype "power_in"))
    )
    (net (code "72") (name "VUSB") (class "Default")
      (node (ref "JP4") (pin "A4") (pinfunction "VBUS_A_A4") (pintype "power_in"))
      (node (ref "JP4") (pin "A9") (pinfunction "VBUS_A_A9") (pintype "power_in"))
      (node (ref "JP4") (pin "B4") (pinfunction "VBUS_B_B4") (pintype "power_in"))
      (node (ref "JP4") (pin "B9") (pinfunction "VBUS_B_B9") (pintype "power_in"))
    )
    (net (code "73") (name "unconnected-(JP4-CC1-PadA5)") (class "Default")
      (node (ref "JP4") (pin "A5") (pinfunction "CC1_A5") (pintype "bidirectional+no_connect"))
    )
    (net (code "74") (name "unconnected-(JP4-CC2-PadB5)") (class "Default")
      (node (ref "JP4") (pin "B5") (pinfunction "CC2_B5") (pintype "bidirectional+no_connect"))
    )
    (net (code "75") (name "unconnected-(JP4-SBU1-PadA8)") (class "Default")
      (node (ref "JP4") (pin "A8") (pinfunction "SBU1_A8") (pintype "bidirectional+no_connect"))
    )
    (net (code "76") (name "unconnected-(JP4-SBU2-PadB8)") (class "Default")
      (node (ref "JP4") (pin "B8") (pinfunction "SBU2_B8") (pintype "bidirectional+no_connect"))
    )
    (net (code "77") (name "unconnected-(JP5-Pad4)") (class "Default")
      (node (ref "JP5") (pin "4") (pinfunction "4_4") (pintype "passive"))
    )
    (net (code "78") (name "unconnected-(M1A-CAM1_C_N-Pad127)") (class "Default")
      (node (ref "M1") (pin "127") (pinfunction "CAM1_C_N_127") (pintype "input+no_connect"))
    )
    (net (code "79") (name "unconnected-(M1A-CAM1_C_P-Pad129)") (class "Default")
      (node (ref "M1") (pin "129") (pinfunction "CAM1_C_P_129") (pintype "input+no_connect"))
    )
    (net (code "80") (name "unconnected-(M1A-CAM1_D0_N-Pad115)") (class "Default")
      (node (ref "M1") (pin "115") (pinfunction "CAM1_D0_N_115") (pintype "input+no_connect"))
    )
    (net (code "81") (name "unconnected-(M1A-CAM1_D0_P-Pad117)") (class "Default")
      (node (ref "M1") (pin "117") (pinfunction "CAM1_D0_P_117") (pintype "input+no_connect"))
    )
    (net (code "82") (name "unconnected-(M1A-CAM1_D1_N-Pad121)") (class "Default")
      (node (ref "M1") (pin "121") (pinfunction "CAM1_D1_N_121") (pintype "input+no_connect"))
    )
    (net (code "83") (name "unconnected-(M1A-CAM1_D1_P-Pad123)") (class "Default")
      (node (ref "M1") (pin "123") (pinfunction "CAM1_D1_P_123") (pintype "input+no_connect"))
    )
    (net (code "84") (name "unconnected-(M1A-CAM1_D2_N-Pad133)") (class "Default")
      (node (ref "M1") (pin "133") (pinfunction "CAM1_D2_N_133") (pintype "input+no_connect"))
    )
    (net (code "85") (name "unconnected-(M1A-CAM1_D2_P-Pad135)") (class "Default")
      (node (ref "M1") (pin "135") (pinfunction "CAM1_D2_P_135") (pintype "input+no_connect"))
    )
    (net (code "86") (name "unconnected-(M1A-CAM1_D3_N-Pad139)") (class "Default")
      (node (ref "M1") (pin "139") (pinfunction "CAM1_D3_N_139") (pintype "input+no_connect"))
    )
    (net (code "87") (name "unconnected-(M1A-CAM1_D3_P-Pad141)") (class "Default")
      (node (ref "M1") (pin "141") (pinfunction "CAM1_D3_P_141") (pintype "input+no_connect"))
    )
    (net (code "88") (name "unconnected-(M1A-DSI0_C_N-Pad169)") (class "Default")
      (node (ref "M1") (pin "169") (pinfunction "DSI0_C_N_169") (pintype "output+no_connect"))
    )
    (net (code "89") (name "unconnected-(M1A-DSI0_C_P-Pad171)") (class "Default")
      (node (ref "M1") (pin "171") (pinfunction "DSI0_C_P_171") (pintype "output+no_connect"))
    )
    (net (code "90") (name "unconnected-(M1A-DSI0_D0_N-Pad157)") (class "Default")
      (node (ref "M1") (pin "157") (pinfunction "DSI0_D0_N_157") (pintype "output+no_connect"))
    )
    (net (code "91") (name "unconnected-(M1A-DSI0_D0_P-Pad159)") (class "Default")
      (node (ref "M1") (pin "159") (pinfunction "DSI0_D0_P_159") (pintype "output+no_connect"))
    )
    (net (code "92") (name "unconnected-(M1A-DSI0_D1_N-Pad163)") (class "Default")
      (node (ref "M1") (pin "163") (pinfunction "DSI0_D1_N_163") (pintype "output+no_connect"))
    )
    (net (code "93") (name "unconnected-(M1A-DSI0_D1_P-Pad165)") (class "Default")
      (node (ref "M1") (pin "165") (pinfunction "DSI0_D1_P_165") (pintype "output+no_connect"))
    )
    (net (code "94") (name "unconnected-(M1A-DSI1_C_N-Pad187)") (class "Default")
      (node (ref "M1") (pin "187") (pinfunction "DSI1_C_N_187") (pintype "output+no_connect"))
    )
    (net (code "95") (name "unconnected-(M1A-DSI1_C_P-Pad189)") (class "Default")
      (node (ref "M1") (pin "189") (pinfunction "DSI1_C_P_189") (pintype "output+no_connect"))
    )
    (net (code "96") (name "unconnected-(M1A-DSI1_D0_N-Pad175)") (class "Default")
      (node (ref "M1") (pin "175") (pinfunction "DSI1_D0_N_175") (pintype "output+no_connect"))
    )
    (net (code "97") (name "unconnected-(M1A-DSI1_D0_P-Pad177)") (class "Default")
      (node (ref "M1") (pin "177") (pinfunction "DSI1_D0_P_177") (pintype "output+no_connect"))
    )
    (net (code "98") (name "unconnected-(M1A-DSI1_D1_N-Pad181)") (class "Default")
      (node (ref "M1") (pin "181") (pinfunction "DSI1_D1_N_181") (pintype "output+no_connect"))
    )
    (net (code "99") (name "unconnected-(M1A-DSI1_D1_P-Pad183)") (class "Default")
      (node (ref "M1") (pin "183") (pinfunction "DSI1_D1_P_183") (pintype "output+no_connect"))
    )
    (net (code "100") (name "unconnected-(M1A-DSI1_D2_N-Pad193)") (class "Default")
      (node (ref "M1") (pin "193") (pinfunction "DSI1_D2_N_193") (pintype "output+no_connect"))
    )
    (net (code "101") (name "unconnected-(M1A-DSI1_D2_P-Pad195)") (class "Default")
      (node (ref "M1") (pin "195") (pinfunction "DSI1_D2_P_195") (pintype "output+no_connect"))
    )
    (net (code "102") (name "unconnected-(M1A-DSI1_D3_N-Pad194)") (class "Default")
      (node (ref "M1") (pin "194") (pinfunction "DSI1_D3_N_194") (pintype "output+no_connect"))
    )
    (net (code "103") (name "unconnected-(M1A-DSI1_D3_P-Pad196)") (class "Default")
      (node (ref "M1") (pin "196") (pinfunction "DSI1_D3_P_196") (pintype "output+no_connect"))
    )
    (net (code "104") (name "unconnected-(M1A-HDMI0_CEC-Pad151)") (class "Default")
      (node (ref "M1") (pin "151") (pinfunction "HDMI0_CEC_151") (pintype "input+no_connect"))
    )
    (net (code "105") (name "unconnected-(M1A-HDMI0_CLK_N-Pad190)") (class "Default")
      (node (ref "M1") (pin "190") (pinfunction "HDMI0_CLK_N_190") (pintype "output+no_connect"))
    )
    (net (code "106") (name "unconnected-(M1A-HDMI0_CLK_P-Pad188)") (class "Default")
      (node (ref "M1") (pin "188") (pinfunction "HDMI0_CLK_P_188") (pintype "output+no_connect"))
    )
    (net (code "107") (name "unconnected-(M1A-HDMI0_HOTPLUG-Pad153)") (class "Default")
      (node (ref "M1") (pin "153") (pinfunction "HDMI0_HOTPLUG_153") (pintype "input+no_connect"))
    )
    (net (code "108") (name "unconnected-(M1A-HDMI0_SCL-Pad200)") (class "Default")
      (node (ref "M1") (pin "200") (pinfunction "HDMI0_SCL_200") (pintype "bidirectional+no_connect"))
    )
    (net (code "109") (name "unconnected-(M1A-HDMI0_SDA-Pad199)") (class "Default")
      (node (ref "M1") (pin "199") (pinfunction "HDMI0_SDA_199") (pintype "bidirectional+no_connect"))
    )
    (net (code "110") (name "unconnected-(M1A-HDMI0_TX0_N-Pad184)") (class "Default")
      (node (ref "M1") (pin "184") (pinfunction "HDMI0_TX0_N_184") (pintype "output+no_connect"))
    )
    (net (code "111") (name "unconnected-(M1A-HDMI0_TX0_P-Pad182)") (class "Default")
      (node (ref "M1") (pin "182") (pinfunction "HDMI0_TX0_P_182") (pintype "output+no_connect"))
    )
    (net (code "112") (name "unconnected-(M1A-HDMI0_TX1_N-Pad178)") (class "Default")
      (node (ref "M1") (pin "178") (pinfunction "HDMI0_TX1_N_178") (pintype "output+no_connect"))
    )
    (net (code "113") (name "unconnected-(M1A-HDMI0_TX1_P-Pad176)") (class "Default")
      (node (ref "M1") (pin "176") (pinfunction "HDMI0_TX1_P_176") (pintype "output+no_connect"))
    )
    (net (code "114") (name "unconnected-(M1A-HDMI0_TX2_N-Pad172)") (class "Default")
      (node (ref "M1") (pin "172") (pinfunction "HDMI0_TX2_N_172") (pintype "output+no_connect"))
    )
    (net (code "115") (name "unconnected-(M1A-HDMI0_TX2_P-Pad170)") (class "Default")
      (node (ref "M1") (pin "170") (pinfunction "HDMI0_TX2_P_170") (pintype "output+no_connect"))
    )
    (net (code "116") (name "unconnected-(M1A-HDMI1_CEC-Pad149)") (class "Default")
      (node (ref "M1") (pin "149") (pinfunction "HDMI1_CEC_149") (pintype "input+no_connect"))
    )
    (net (code "117") (name "unconnected-(M1A-HDMI1_CLK_N-Pad166)") (class "Default")
      (node (ref "M1") (pin "166") (pinfunction "HDMI1_CLK_N_166") (pintype "output+no_connect"))
    )
    (net (code "118") (name "unconnected-(M1A-HDMI1_CLK_P-Pad164)") (class "Default")
      (node (ref "M1") (pin "164") (pinfunction "HDMI1_CLK_P_164") (pintype "output+no_connect"))
    )
    (net (code "119") (name "unconnected-(M1A-HDMI1_HOTPLUG-Pad143)") (class "Default")
      (node (ref "M1") (pin "143") (pinfunction "HDMI1_HOTPLUG_143") (pintype "input+no_connect"))
    )
    (net (code "120") (name "unconnected-(M1A-HDMI1_SCL-Pad147)") (class "Default")
      (node (ref "M1") (pin "147") (pinfunction "HDMI1_SCL_147") (pintype "bidirectional+no_connect"))
    )
    (net (code "121") (name "unconnected-(M1A-HDMI1_SDA-Pad145)") (class "Default")
      (node (ref "M1") (pin "145") (pinfunction "HDMI1_SDA_145") (pintype "bidirectional+no_connect"))
    )
    (net (code "122") (name "unconnected-(M1A-HDMI1_TX0_N-Pad160)") (class "Default")
      (node (ref "M1") (pin "160") (pinfunction "HDMI1_TX0_N_160") (pintype "output+no_connect"))
    )
    (net (code "123") (name "unconnected-(M1A-HDMI1_TX0_P-Pad158)") (class "Default")
      (node (ref "M1") (pin "158") (pinfunction "HDMI1_TX0_P_158") (pintype "output+no_connect"))
    )
    (net (code "124") (name "unconnected-(M1A-HDMI1_TX1_N-Pad154)") (class "Default")
      (node (ref "M1") (pin "154") (pinfunction "HDMI1_TX1_N_154") (pintype "output+no_connect"))
    )
    (net (code "125") (name "unconnected-(M1A-HDMI1_TX1_P-Pad152)") (class "Default")
      (node (ref "M1") (pin "152") (pinfunction "HDMI1_TX1_P_152") (pintype "output+no_connect"))
    )
    (net (code "126") (name "unconnected-(M1A-HDMI1_TX2_N-Pad148)") (class "Default")
      (node (ref "M1") (pin "148") (pinfunction "HDMI1_TX2_N_148") (pintype "output+no_connect"))
    )
    (net (code "127") (name "unconnected-(M1A-HDMI1_TX2_P-Pad146)") (class "Default")
      (node (ref "M1") (pin "146") (pinfunction "HDMI1_TX2_P_146") (pintype "output+no_connect"))
    )
    (net (code "128") (name "unconnected-(M1A-PCIE_!RST-Pad109)") (class "Default")
      (node (ref "M1") (pin "109") (pinfunction "PCIE_!RST_109") (pintype "output+no_connect"))
    )
    (net (code "129") (name "unconnected-(M1A-PCIE_CLK_!REQ-Pad102)") (class "Default")
      (node (ref "M1") (pin "102") (pinfunction "PCIE_CLK_!REQ_102") (pintype "input+no_connect"))
    )
    (net (code "130") (name "unconnected-(M1A-PCIE_CLK_N-Pad112)") (class "Default")
      (node (ref "M1") (pin "112") (pinfunction "PCIE_CLK_N_112") (pintype "output+no_connect"))
    )
    (net (code "131") (name "unconnected-(M1A-PCIE_CLK_P-Pad110)") (class "Default")
      (node (ref "M1") (pin "110") (pinfunction "PCIE_CLK_P_110") (pintype "output+no_connect"))
    )
    (net (code "132") (name "unconnected-(M1A-PCIE_RX_N-Pad118)") (class "Default")
      (node (ref "M1") (pin "118") (pinfunction "PCIE_RX_N_118") (pintype "input+no_connect"))
    )
    (net (code "133") (name "unconnected-(M1A-PCIE_RX_P-Pad116)") (class "Default")
      (node (ref "M1") (pin "116") (pinfunction "PCIE_RX_P_116") (pintype "input+no_connect"))
    )
    (net (code "134") (name "unconnected-(M1A-PCIE_TX_N-Pad124)") (class "Default")
      (node (ref "M1") (pin "124") (pinfunction "PCIE_TX_N_124") (pintype "output+no_connect"))
    )
    (net (code "135") (name "unconnected-(M1A-PCIE_TX_P-Pad122)") (class "Default")
      (node (ref "M1") (pin "122") (pinfunction "PCIE_TX_P_122") (pintype "output+no_connect"))
    )
    (net (code "136") (name "unconnected-(M1A-VDAC_COMP-Pad111)") (class "Default")
      (node (ref "M1") (pin "111") (pinfunction "VDAC_COMP_111") (pintype "output+no_connect"))
    )
    (net (code "137") (name "unconnected-(M1B-BT_!DISABLE-Pad91)") (class "Default")
      (node (ref "M1") (pin "91") (pinfunction "BT_!DISABLE_91") (pintype "input+no_connect"))
    )
    (net (code "138") (name "unconnected-(M1B-CM4_1.8V(OUTPUT)-Pad88)") (class "Default")
      (node (ref "M1") (pin "88") (pinfunction "CM4_1.8V(OUTPUT)_88") (pintype "power_in+no_connect"))
    )
    (net (code "139") (name "unconnected-(M1B-CM4_1.8V(OUTPUT)-Pad90)") (class "Default")
      (node (ref "M1") (pin "90") (pinfunction "CM4_1.8V(OUTPUT)_90") (pintype "power_in+no_connect"))
    )
    (net (code "140") (name "unconnected-(M1B-CM4_3.3V(OUTPUT)-Pad84)") (class "Default")
      (node (ref "M1") (pin "84") (pinfunction "CM4_3.3V(OUTPUT)_84") (pintype "power_in+no_connect"))
    )
    (net (code "141") (name "unconnected-(M1B-CM4_3.3V(OUTPUT)-Pad86)") (class "Default")
      (node (ref "M1") (pin "86") (pinfunction "CM4_3.3V(OUTPUT)_86") (pintype "power_in+no_connect"))
    )
    (net (code "142") (name "unconnected-(M1B-ETHERNET_!LED1-Pad19)") (class "Default")
      (node (ref "M1") (pin "19") (pinfunction "ETHERNET_!LED1_19") (pintype "output+no_connect"))
    )
    (net (code "143") (name "unconnected-(M1B-ETHERNET_!LED2-Pad17)") (class "Default")
      (node (ref "M1") (pin "17") (pinfunction "ETHERNET_!LED2_17") (pintype "output+no_connect"))
    )
    (net (code "144") (name "unconnected-(M1B-ETHERNET_!LED3-Pad15)") (class "Default")
      (node (ref "M1") (pin "15") (pinfunction "ETHERNET_!LED3_15") (pintype "output+no_connect"))
    )
    (net (code "145") (name "unconnected-(M1B-ETHERNET_PAIR0_N-Pad10)") (class "Default")
      (node (ref "M1") (pin "10") (pinfunction "ETHERNET_PAIR0_N_10") (pintype "bidirectional+no_connect"))
    )
    (net (code "146") (name "unconnected-(M1B-ETHERNET_PAIR0_P-Pad12)") (class "Default")
      (node (ref "M1") (pin "12") (pinfunction "ETHERNET_PAIR0_P_12") (pintype "bidirectional+no_connect"))
    )
    (net (code "147") (name "unconnected-(M1B-ETHERNET_PAIR1_N-Pad6)") (class "Default")
      (node (ref "M1") (pin "6") (pinfunction "ETHERNET_PAIR1_N_6") (pintype "bidirectional+no_connect"))
    )
    (net (code "148") (name "unconnected-(M1B-ETHERNET_PAIR1_P-Pad4)") (class "Default")
      (node (ref "M1") (pin "4") (pinfunction "ETHERNET_PAIR1_P_4") (pintype "bidirectional+no_connect"))
    )
    (net (code "149") (name "unconnected-(M1B-ETHERNET_PAIR2_N-Pad9)") (class "Default")
      (node (ref "M1") (pin "9") (pinfunction "ETHERNET_PAIR2_N_9") (pintype "bidirectional+no_connect"))
    )
    (net (code "150") (name "unconnected-(M1B-ETHERNET_PAIR2_P-Pad11)") (class "Default")
      (node (ref "M1") (pin "11") (pinfunction "ETHERNET_PAIR2_P_11") (pintype "bidirectional+no_connect"))
    )
    (net (code "151") (name "unconnected-(M1B-ETHERNET_PAIR3_N-Pad5)") (class "Default")
      (node (ref "M1") (pin "5") (pinfunction "ETHERNET_PAIR3_N_5") (pintype "bidirectional+no_connect"))
    )
    (net (code "152") (name "unconnected-(M1B-ETHERNET_PAIR3_P-Pad3)") (class "Default")
      (node (ref "M1") (pin "3") (pinfunction "ETHERNET_PAIR3_P_3") (pintype "bidirectional+no_connect"))
    )
    (net (code "153") (name "unconnected-(M1B-ETHERNET_SYNC_IN-Pad16)") (class "Default")
      (node (ref "M1") (pin "16") (pinfunction "ETHERNET_SYNC_IN_16") (pintype "input+no_connect"))
    )
    (net (code "154") (name "unconnected-(M1B-ETHERNET_SYNC_OUT-Pad18)") (class "Default")
      (node (ref "M1") (pin "18") (pinfunction "ETHERNET_SYNC_OUT_18") (pintype "output+no_connect"))
    )
    (net (code "155") (name "unconnected-(M1B-GLOBAL_EN-Pad99)") (class "Default")
      (node (ref "M1") (pin "99") (pinfunction "GLOBAL_EN_99") (pintype "input+no_connect"))
    )
    (net (code "156") (name "unconnected-(M1B-GPIO4-Pad54)") (class "Default")
      (node (ref "M1") (pin "54") (pinfunction "GPIO4_54") (pintype "bidirectional"))
    )
    (net (code "157") (name "unconnected-(M1B-GPIO7-Pad37)") (class "Default")
      (node (ref "M1") (pin "37") (pinfunction "GPIO7_37") (pintype "bidirectional"))
    )
    (net (code "158") (name "unconnected-(M1B-GPIO8-Pad39)") (class "Default")
      (node (ref "M1") (pin "39") (pinfunction "GPIO8_39") (pintype "bidirectional"))
    )
    (net (code "159") (name "unconnected-(M1B-GPIO17-Pad50)") (class "Default")
      (node (ref "M1") (pin "50") (pinfunction "GPIO17_50") (pintype "bidirectional"))
    )
    (net (code "160") (name "unconnected-(M1B-GPIO19-Pad26)") (class "Default")
      (node (ref "M1") (pin "26") (pinfunction "GPIO19_26") (pintype "bidirectional"))
    )
    (net (code "161") (name "unconnected-(M1B-GPIO26-Pad24)") (class "Default")
      (node (ref "M1") (pin "24") (pinfunction "GPIO26_24") (pintype "bidirectional"))
    )
    (net (code "162") (name "unconnected-(M1B-GPIO27-Pad48)") (class "Default")
      (node (ref "M1") (pin "48") (pinfunction "GPIO27_48") (pintype "bidirectional"))
    )
    (net (code "163") (name "unconnected-(M1B-RESERVED-Pad76)") (class "Default")
      (node (ref "M1") (pin "76") (pinfunction "RESERVED_76") (pintype "passive+no_connect"))
    )
    (net (code "164") (name "unconnected-(M1B-RESERVED-Pad104)") (class "Default")
      (node (ref "M1") (pin "104") (pinfunction "RESERVED_104") (pintype "passive+no_connect"))
    )
    (net (code "165") (name "unconnected-(M1B-RESERVED-Pad106)") (class "Default")
      (node (ref "M1") (pin "106") (pinfunction "RESERVED_106") (pintype "passive+no_connect"))
    )
    (net (code "166") (name "unconnected-(M1B-RUN_PG-Pad92)") (class "Default")
      (node (ref "M1") (pin "92") (pinfunction "RUN_PG_92") (pintype "bidirectional"))
    )
    (net (code "167") (name "unconnected-(M1B-SD_CLK-Pad57)") (class "Default")
      (node (ref "M1") (pin "57") (pinfunction "SD_CLK_57") (pintype "bidirectional+no_connect"))
    )
    (net (code "168") (name "unconnected-(M1B-SD_CMD-Pad62)") (class "Default")
      (node (ref "M1") (pin "62") (pinfunction "SD_CMD_62") (pintype "input+no_connect"))
    )
    (net (code "169") (name "unconnected-(M1B-SD_DAT0-Pad63)") (class "Default")
      (node (ref "M1") (pin "63") (pinfunction "SD_DAT0_63") (pintype "bidirectional+no_connect"))
    )
    (net (code "170") (name "unconnected-(M1B-SD_DAT1-Pad67)") (class "Default")
      (node (ref "M1") (pin "67") (pinfunction "SD_DAT1_67") (pintype "bidirectional+no_connect"))
    )
    (net (code "171") (name "unconnected-(M1B-SD_DAT2-Pad69)") (class "Default")
      (node (ref "M1") (pin "69") (pinfunction "SD_DAT2_69") (pintype "bidirectional+no_connect"))
    )
    (net (code "172") (name "unconnected-(M1B-SD_DAT3-Pad61)") (class "Default")
      (node (ref "M1") (pin "61") (pinfunction "SD_DAT3_61") (pintype "bidirectional+no_connect"))
    )
    (net (code "173") (name "unconnected-(M1B-SD_DAT4-Pad68)") (class "Default")
      (node (ref "M1") (pin "68") (pinfunction "SD_DAT4_68") (pintype "bidirectional+no_connect"))
    )
    (net (code "174") (name "unconnected-(M1B-SD_DAT5-Pad64)") (class "Default")
      (node (ref "M1") (pin "64") (pinfunction "SD_DAT5_64") (pintype "bidirectional+no_connect"))
    )
    (net (code "175") (name "unconnected-(M1B-SD_DAT6-Pad72)") (class "Default")
      (node (ref "M1") (pin "72") (pinfunction "SD_DAT6_72") (pintype "bidirectional+no_connect"))
    )
    (net (code "176") (name "unconnected-(M1B-SD_DAT7-Pad70)") (class "Default")
      (node (ref "M1") (pin "70") (pinfunction "SD_DAT7_70") (pintype "bidirectional+no_connect"))
    )
    (net (code "177") (name "unconnected-(M1B-SD_PWR_ON-Pad75)") (class "Default")
      (node (ref "M1") (pin "75") (pinfunction "SD_PWR_ON_75") (pintype "output+no_connect"))
    )
    (net (code "178") (name "unconnected-(M1B-SD_VDD_OVERRIDE-Pad73)") (class "Default")
      (node (ref "M1") (pin "73") (pinfunction "SD_VDD_OVERRIDE_73") (pintype "input+no_connect"))
    )
    (net (code "179") (name "unconnected-(M1B-WL_!DISABLE-Pad89)") (class "Default")
      (node (ref "M1") (pin "89") (pinfunction "WL_!DISABLE_89") (pintype "input+no_connect"))
    )
    (net (code "180") (name "unconnected-(M1B-~{EXTRST}-Pad100)") (class "Default")
      (node (ref "M1") (pin "100") (pinfunction "~{EXTRST}_100") (pintype "output+no_connect"))
    )
    (net (code "181") (name "unconnected-(RA1-Pad4)") (class "Default")
      (node (ref "RA1") (pin "4") (pinfunction "4_4") (pintype "passive+no_connect"))
    )
    (net (code "182") (name "unconnected-(RA1-Pad5)") (class "Default")
      (node (ref "RA1") (pin "5") (pinfunction "5_5") (pintype "passive+no_connect"))
    )
  )
)
